# Audio_Output.net
KiCad netlist of a schematic drawn in EAGLE
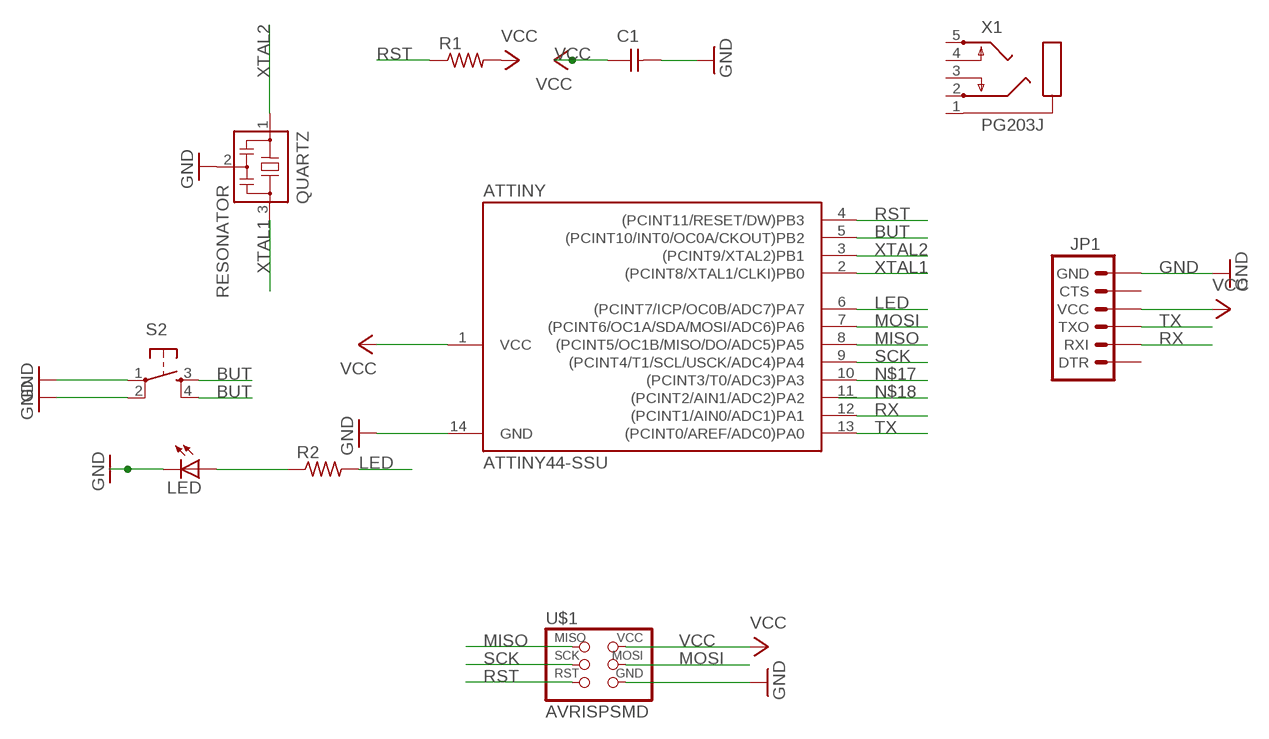
[diagram p0: schematic, sheet 1]

(export (version "E")
  (design (tool "Eeschema 10.0.6"))
  (components
    (comp (ref "ATTINY")
      (value "ATTINY44-SSU")
      (footprint "eagle-import:SOIC14")
      (libsource (lib "eagle-import") (part "ATTINY44-SSU"))
    )
    (comp (ref "C1")
      (value "UNPOLARIZED_CAPACITOR1206")
      (footprint "eagle-import:1206")
      (libsource (lib "eagle-import") (part "UNPOLARIZED_CAPACITOR1206"))
    )
    (comp (ref "JP1")
      (value "ARDUINO_SERIAL_PROGRAMLONGPADS")
      (footprint "eagle-import:1X06_LONGPADS")
      (libsource (lib "eagle-import") (part "ARDUINO_SERIAL_PROGRAMLONGPADS"))
    )
    (comp (ref "LED")
      (value "LED1206")
      (footprint "eagle-import:1206")
      (libsource (lib "eagle-import") (part "LED1206"))
    )
    (comp (ref "QUARTZ")
      (value "RESONATOR")
      (footprint "eagle-import:EFOBM")
      (libsource (lib "eagle-import") (part "RESONATOR"))
    )
    (comp (ref "R1")
      (value "RESISTOR1206")
      (footprint "eagle-import:1206")
      (libsource (lib "eagle-import") (part "RESISTOR1206"))
    )
    (comp (ref "R2")
      (value "RESISTOR1206")
      (footprint "eagle-import:1206")
      (libsource (lib "eagle-import") (part "RESISTOR1206"))
    )
    (comp (ref "S2")
      (value "6MM_SWITCH6MM_SWITCH")
      (footprint "eagle-import:6MM_SWITCH")
      (libsource (lib "eagle-import") (part "6MM_SWITCH6MM_SWITCH"))
    )
    (comp (ref "U$1")
      (value "AVRISPSMD")
      (footprint "eagle-import:2X03SMD")
      (libsource (lib "eagle-import") (part "AVRISPSMD"))
    )
    (comp (ref "X1")
      (value "PG203J")
      (footprint "eagle-import:PG203J")
      (libsource (lib "eagle-import") (part "PG203J"))
    )
  )
  (nets
    (net (code "1") (name "/BUT") (class "Default")
      (node (ref "ATTINY") (pin "5") (pinfunction "(PCINT10/INT0/OC0A/CKOUT)PB2_5") (pintype "bidirectional"))
      (node (ref "S2") (pin "3") (pinfunction "S_3") (pintype "passive"))
      (node (ref "S2") (pin "4") (pinfunction "S1_4") (pintype "passive"))
    )
    (net (code "2") (name "/LED") (class "Default")
      (node (ref "ATTINY") (pin "6") (pinfunction "(PCINT7/ICP/OC0B/ADC7)PA7_6") (pintype "bidirectional"))
      (node (ref "R2") (pin "2") (pinfunction "2_2") (pintype "passive"))
    )
    (net (code "3") (name "/MISO") (class "Default")
      (node (ref "ATTINY") (pin "8") (pinfunction "(PCINT5/OC1B/MISO/DO/ADC5)PA5_8") (pintype "bidirectional"))
      (node (ref "U$1") (pin "1") (pinfunction "MISO_1") (pintype "passive"))
    )
    (net (code "4") (name "/MOSI") (class "Default")
      (node (ref "ATTINY") (pin "7") (pinfunction "(PCINT6/OC1A/SDA/MOSI/ADC6)PA6_7") (pintype "bidirectional"))
      (node (ref "U$1") (pin "4") (pinfunction "MOSI_4") (pintype "passive"))
    )
    (net (code "5") (name "/N$17") (class "Default")
      (node (ref "ATTINY") (pin "10") (pinfunction "(PCINT3/T0/ADC3)PA3_10") (pintype "bidirectional"))
    )
    (net (code "7") (name "/RST") (class "Default")
      (node (ref "ATTINY") (pin "4") (pinfunction "(PCINT11/RESET/DW)PB3_4") (pintype "bidirectional"))
      (node (ref "R1") (pin "1") (pinfunction "1_1") (pintype "passive"))
      (node (ref "U$1") (pin "5") (pinfunction "RST_5") (pintype "passive"))
    )
    (net (code "8") (name "/RX") (class "Default")
      (node (ref "ATTINY") (pin "12") (pinfunction "(PCINT1/AIN0/ADC1)PA1_12") (pintype "bidirectional"))
      (node (ref "JP1") (pin "2") (pinfunction "RXI_2") (pintype "passive"))
    )
    (net (code "9") (name "/SCK") (class "Default")
      (node (ref "ATTINY") (pin "9") (pinfunction "(PCINT4/T1/SCL/USCK/ADC4)PA4_9") (pintype "bidirectional"))
      (node (ref "U$1") (pin "3") (pinfunction "SCK_3") (pintype "passive"))
    )
    (net (code "10") (name "/TX") (class "Default")
      (node (ref "ATTINY") (pin "13") (pinfunction "(PCINT0/AREF/ADC0)PA0_13") (pintype "bidirectional"))
      (node (ref "JP1") (pin "3") (pinfunction "TXO_3") (pintype "passive"))
    )
    (net (code "11") (name "/XTAL1") (class "Default")
      (node (ref "ATTINY") (pin "2") (pinfunction "(PCINT8/XTAL1/CLKI)PB0_2") (pintype "bidirectional"))
      (node (ref "QUARTZ") (pin "3") (pinfunction "3_3") (pintype "passive"))
    )
    (net (code "12") (name "/XTAL2") (class "Default")
      (node (ref "ATTINY") (pin "3") (pinfunction "(PCINT9/XTAL2)PB1_3") (pintype "bidirectional"))
      (node (ref "QUARTZ") (pin "1") (pinfunction "1_1") (pintype "passive"))
    )
    (net (code "13") (name "GND") (class "Default")
      (node (ref "ATTINY") (pin "14") (pinfunction "GND_14") (pintype "power_in"))
      (node (ref "C1") (pin "2") (pinfunction "2_2") (pintype "passive"))
      (node (ref "JP1") (pin "6") (pinfunction "GND_6") (pintype "passive"))
      (node (ref "LED") (pin "2") (pinfunction "C_2") (pintype "passive"))
      (node (ref "QUARTZ") (pin "2") (pinfunction "2_2") (pintype "passive"))
      (node (ref "S2") (pin "1") (pinfunction "P_1") (pintype "passive"))
      (node (ref "S2") (pin "2") (pinfunction "P1_2") (pintype "passive"))
      (node (ref "U$1") (pin "6") (pinfunction "GND_6") (pintype "passive"))
    )
    (net (code "14") (name "Net-(LED-A)") (class "Default")
      (node (ref "LED") (pin "1") (pinfunction "A_1") (pintype "passive"))
      (node (ref "R2") (pin "1") (pinfunction "1_1") (pintype "passive"))
    )
    (net (code "15") (name "VCC") (class "Default")
      (node (ref "ATTINY") (pin "1") (pinfunction "VCC_1") (pintype "power_in"))
      (node (ref "C1") (pin "1") (pinfunction "1_1") (pintype "passive"))
      (node (ref "JP1") (pin "4") (pinfunction "VCC_4") (pintype "passive"))
      (node (ref "R1") (pin "2") (pinfunction "2_2") (pintype "passive"))
      (node (ref "U$1") (pin "2") (pinfunction "VCC_2") (pintype "passive"))
    )
    (net (code "16") (name "unconnected-(ATTINY-(PCINT2{slash}AIN1{slash}ADC2)PA2-Pad11)") (class "Default")
      (node (ref "ATTINY") (pin "11") (pinfunction "(PCINT2/AIN1/ADC2)PA2_11") (pintype "bidirectional"))
    )
    (net (code "17") (name "unconnected-(JP1-CTS-Pad5)") (class "Default")
      (node (ref "JP1") (pin "5") (pinfunction "CTS_5") (pintype "passive"))
    )
    (net (code "18") (name "unconnected-(JP1-DTR-Pad1)") (class "Default")
      (node (ref "JP1") (pin "1") (pinfunction "DTR_1") (pintype "passive"))
    )
    (net (code "19") (name "unconnected-(X1-Pad1)") (class "Default")
      (node (ref "X1") (pin "1") (pinfunction "1_1") (pintype "passive"))
    )
    (net (code "20") (name "unconnected-(X1-Pad2)") (class "Default")
      (node (ref "X1") (pin "2") (pinfunction "2_2") (pintype "passive"))
    )
    (net (code "21") (name "unconnected-(X1-Pad3)") (class "Default")
      (node (ref "X1") (pin "3") (pinfunction "3_3") (pintype "passive"))
    )
    (net (code "22") (name "unconnected-(X1-Pad4)") (class "Default")
      (node (ref "X1") (pin "4") (pinfunction "4_4") (pintype "passive"))
    )
    (net (code "23") (name "unconnected-(X1-Pad5)") (class "Default")
      (node (ref "X1") (pin "5") (pinfunction "5_5") (pintype "passive"))
    )
  )
)
